# Barrido_de_doble_fuente_DC.net
KiCad netlist of a schematic drawn in Altium Designer
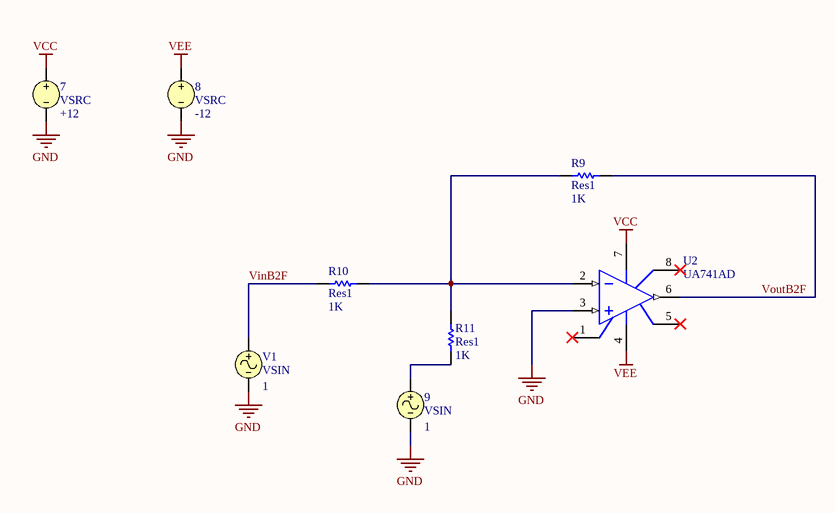
[diagram p0: Barrido de doble fuente DC.SchDoc]

(export (version "E")
  (design (tool "Eeschema 10.0.6"))
  (components
    (comp (ref "7")
      (value "VSRC")
      (description "Voltage Source")
      (fields (field (name "ALTIUM_VALUE") "+12") (field (name "PUBLISHER") "Altium Limited"))
      (libsource (lib "Simulation Sources") (part "VSRC"))
    )
    (comp (ref "8")
      (value "VSRC")
      (description "Voltage Source")
      (fields (field (name "ALTIUM_VALUE") "-12") (field (name "PUBLISHER") "Altium Limited"))
      (libsource (lib "Simulation Sources") (part "VSRC"))
    )
    (comp (ref "9")
      (value "VSIN")
      (description "Sinusoidal Voltage Source")
      (fields (field (name "AMPLITUDE") "1") (field (name "PUBLISHER") "Altium Limited"))
      (libsource (lib "Simulation Sources") (part "VSIN"))
    )
    (comp (ref "R9")
      (value "Res1")
      (footprint "AXIAL-0.3")
      (description "Resistor")
      (fields (field (name "ALTIUM_VALUE") "1K") (field (name "PUBLISHER") "Altium Limited"))
      (libsource (lib "Miscellaneous Devices") (part "Res1"))
    )
    (comp (ref "R10")
      (value "Res1")
      (footprint "AXIAL-0.3")
      (description "Resistor")
      (fields (field (name "ALTIUM_VALUE") "1K") (field (name "PUBLISHER") "Altium Limited"))
      (libsource (lib "Miscellaneous Devices") (part "Res1"))
    )
    (comp (ref "R11")
      (value "Res1")
      (footprint "AXIAL-0.3")
      (description "Resistor")
      (fields (field (name "ALTIUM_VALUE") "1K") (field (name "PUBLISHER") "Altium Limited"))
      (libsource (lib "Miscellaneous Devices") (part "Res1"))
    )
    (comp (ref "U2")
      (value "UA741AD")
      (footprint "SO8_L")
      (description "General-Purpose Single Operational Amplifier")
      (fields (field (name "PUBLISHER") "Altium Limited"))
      (libsource (lib "ST Operational Amplifier") (part "UA741AD"))
    )
    (comp (ref "V1")
      (value "VSIN")
      (description "Sinusoidal Voltage Source")
      (fields (field (name "AMPLITUDE") "1") (field (name "PUBLISHER") "Altium Limited"))
      (libsource (lib "Simulation Sources") (part "VSIN"))
    )
  )
  (nets
    (net (code "1") (name "/VinB2F") (class "Default")
      (node (ref "R10") (pin "1") (pinfunction "1_1") (pintype "passive"))
      (node (ref "V1") (pin "1") (pinfunction "1_1") (pintype "passive"))
    )
    (net (code "2") (name "/VoutB2F") (class "Default")
      (node (ref "R9") (pin "2") (pinfunction "2_2") (pintype "passive"))
      (node (ref "U2") (pin "6") (pinfunction "OUT_6") (pintype "output"))
    )
    (net (code "3") (name "GND") (class "Default")
      (node (ref "7") (pin "2") (pinfunction "2_2") (pintype "passive"))
      (node (ref "8") (pin "2") (pinfunction "2_2") (pintype "passive"))
      (node (ref "9") (pin "2") (pinfunction "2_2") (pintype "passive"))
      (node (ref "U2") (pin "3") (pinfunction "IN+_3") (pintype "input"))
      (node (ref "V1") (pin "2") (pinfunction "2_2") (pintype "passive"))
    )
    (net (code "4") (name "Net-(9-Pad1)") (class "Default")
      (node (ref "9") (pin "1") (pinfunction "1_1") (pintype "passive"))
      (node (ref "R11") (pin "1") (pinfunction "1_1") (pintype "passive"))
    )
    (net (code "5") (name "Net-(U2-IN-)") (class "Default")
      (node (ref "R10") (pin "2") (pinfunction "2_2") (pintype "passive"))
      (node (ref "R11") (pin "2") (pinfunction "2_2") (pintype "passive"))
      (node (ref "R9") (pin "1") (pinfunction "1_1") (pintype "passive"))
      (node (ref "U2") (pin "2") (pinfunction "IN-_2") (pintype "input"))
    )
    (net (code "6") (name "VCC") (class "Default")
      (node (ref "7") (pin "1") (pinfunction "1_1") (pintype "passive"))
      (node (ref "U2") (pin "7") (pinfunction "V+_7") (pintype "power_in"))
    )
    (net (code "7") (name "VEE") (class "Default")
      (node (ref "8") (pin "1") (pinfunction "1_1") (pintype "passive"))
      (node (ref "U2") (pin "4") (pinfunction "V-_4") (pintype "power_in"))
    )
    (net (code "8") (name "unconnected-(U2-NC-Pad8)") (class "Default")
      (node (ref "U2") (pin "8") (pinfunction "NC_8") (pintype "passive+no_connect"))
    )
    (net (code "9") (name "unconnected-(U2-OS_NULL-Pad1)") (class "Default")
      (node (ref "U2") (pin "1") (pinfunction "OS_NULL_1") (pintype "passive+no_connect"))
    )
    (net (code "10") (name "unconnected-(U2-OS_NULL-Pad5)") (class "Default")
      (node (ref "U2") (pin "5") (pinfunction "OS_NULL_5") (pintype "passive+no_connect"))
    )
  )
)
